# PWR_APD5052.net
KiCad netlist of a schematic drawn in Altium Designer
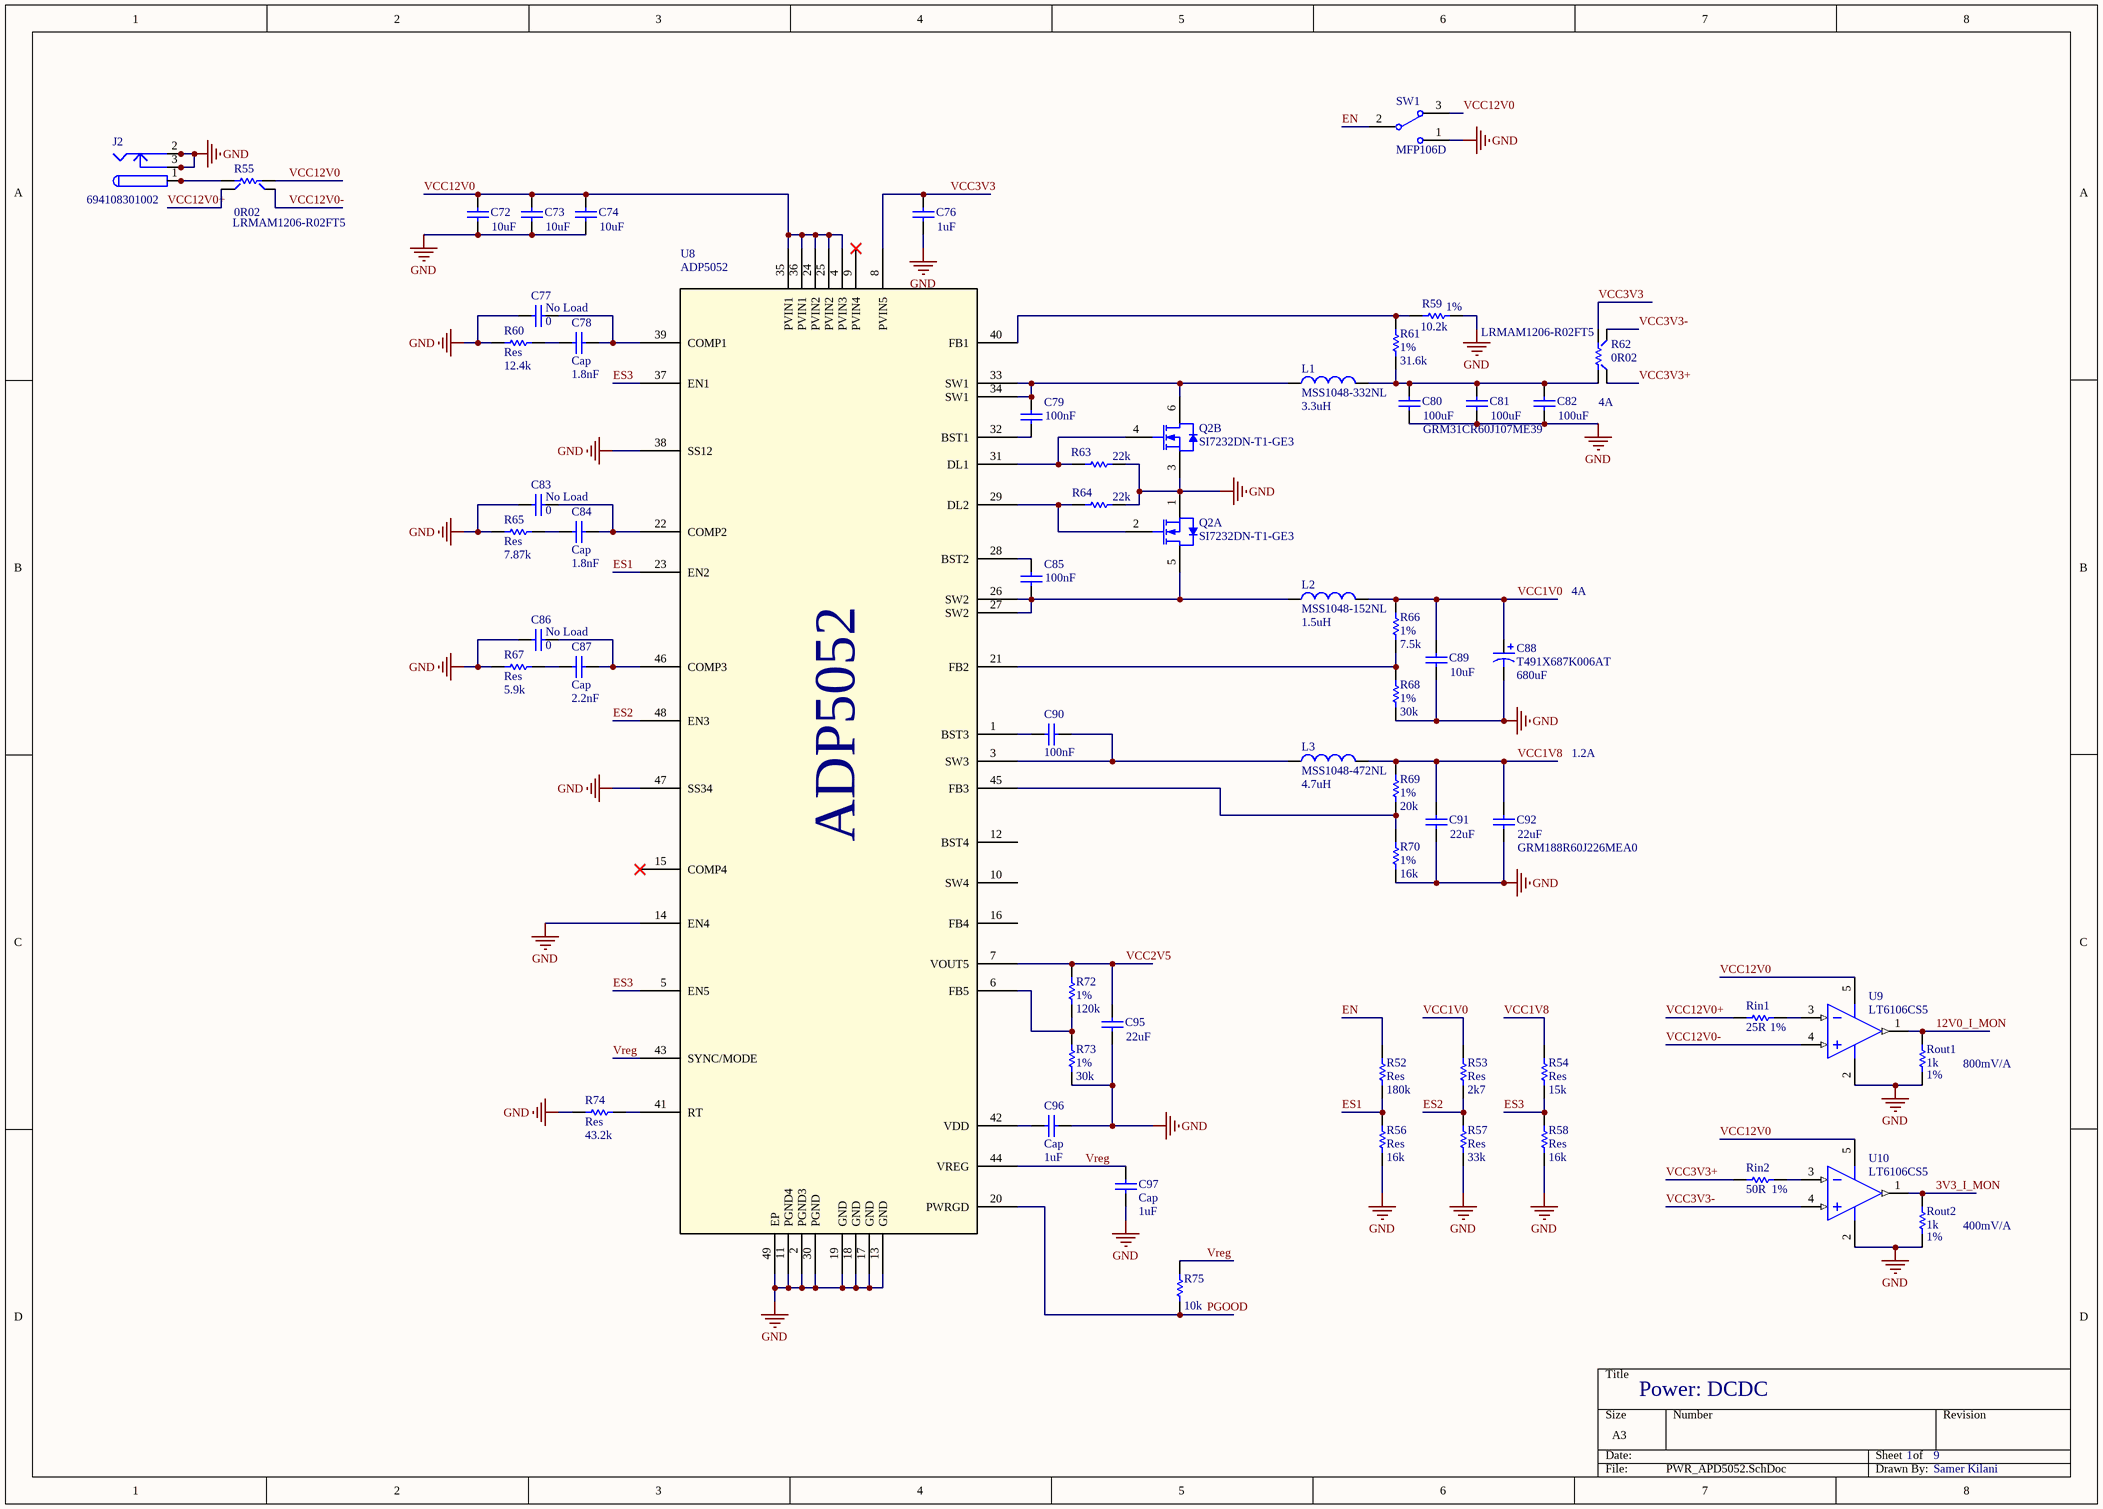
[diagram p0: PWR_APD5052.SchDoc]

(export (version "E")
  (design (tool "Eeschema 10.0.6"))
  (components
    (comp (ref "C72")
      (value "10uF")
      (footprint "C0805")
      (description "Capacitor")
      (fields (field (name "PUBLISHER") "Altium Limited"))
      (libsource (lib "atfclib") (part "Cap"))
    )
    (comp (ref "C73")
      (value "10uF")
      (footprint "C0805")
      (description "Capacitor")
      (fields (field (name "PUBLISHER") "Altium Limited"))
      (libsource (lib "atfclib") (part "Cap"))
    )
    (comp (ref "C74")
      (value "10uF")
      (footprint "C0805")
      (description "Capacitor")
      (fields (field (name "Comment") "Cap") (field (name "PUBLISHER") "Altium Limited"))
      (libsource (lib "atfclib") (part "Cap"))
    )
    (comp (ref "C76")
      (value "1uF")
      (footprint "C0402")
      (description "Capacitor")
      (fields (field (name "PUBLISHER") "Altium Limited"))
      (libsource (lib "atfclib") (part "Cap"))
    )
    (comp (ref "C77")
      (value "No Load")
      (footprint "C0402")
      (description "Capacitor")
      (fields (field (name "ALTIUM_VALUE") "0") (field (name "PUBLISHER") "Altium Limited"))
      (libsource (lib "atfclib") (part "Cap"))
    )
    (comp (ref "C78")
      (value "Cap")
      (footprint "C0402")
      (description "Capacitor")
      (fields (field (name "ALTIUM_VALUE") "1.8nF") (field (name "PUBLISHER") "Altium Limited"))
      (libsource (lib "atfclib") (part "Cap"))
    )
    (comp (ref "C79")
      (value "100nF")
      (footprint "C0402")
      (description "Capacitor")
      (fields (field (name "Comment") "Cap") (field (name "PUBLISHER") "Altium Limited"))
      (libsource (lib "atfclib") (part "Cap"))
    )
    (comp (ref "C80")
      (value "GRM31CR60J107ME39")
      (footprint "C1206")
      (description "Capacitor")
      (fields (field (name "ALTIUM_VALUE") "100uF") (field (name "PUBLISHER") "Altium Limited"))
      (libsource (lib "atfclib") (part "Cap"))
    )
    (comp (ref "C81")
      (value "100uF")
      (footprint "C1206")
      (description "Capacitor")
      (fields (field (name "Comment") "GRM31CR60J107ME39") (field (name "PUBLISHER") "Altium Limited"))
      (libsource (lib "atfclib") (part "Cap"))
    )
    (comp (ref "C82")
      (value "100uF")
      (footprint "C1206")
      (description "Capacitor")
      (fields (field (name "Comment") "GRM31CR60J107ME39") (field (name "PUBLISHER") "Altium Limited"))
      (libsource (lib "atfclib") (part "Cap"))
    )
    (comp (ref "C83")
      (value "No Load")
      (footprint "C0402")
      (description "Capacitor")
      (fields (field (name "ALTIUM_VALUE") "0") (field (name "PUBLISHER") "Altium Limited"))
      (libsource (lib "atfclib") (part "Cap"))
    )
    (comp (ref "C84")
      (value "Cap")
      (footprint "C0402")
      (description "Capacitor")
      (fields (field (name "ALTIUM_VALUE") "1.8nF") (field (name "PUBLISHER") "Altium Limited"))
      (libsource (lib "atfclib") (part "Cap"))
    )
    (comp (ref "C85")
      (value "100nF")
      (footprint "C0402")
      (description "Capacitor")
      (fields (field (name "Comment") "Cap") (field (name "PUBLISHER") "Altium Limited"))
      (libsource (lib "atfclib") (part "Cap"))
    )
    (comp (ref "C86")
      (value "No Load")
      (footprint "C0402")
      (description "Capacitor")
      (fields (field (name "ALTIUM_VALUE") "0") (field (name "PUBLISHER") "Altium Limited"))
      (libsource (lib "atfclib") (part "Cap"))
    )
    (comp (ref "C87")
      (value "Cap")
      (footprint "C0402")
      (description "Capacitor")
      (fields (field (name "ALTIUM_VALUE") "2.2nF") (field (name "PUBLISHER") "Altium Limited"))
      (libsource (lib "atfclib") (part "Cap"))
    )
    (comp (ref "C88")
      (value "T491X687K006AT")
      (footprint "C7343")
      (description "Polarized Capacitor (Surface Mount)")
      (fields (field (name "ALTIUM_VALUE") "680uF") (field (name "PUBLISHER") "Altium Limited"))
      (libsource (lib "Miscellaneous Devices") (part "Cap Pol3"))
    )
    (comp (ref "C89")
      (value "10uF")
      (footprint "C0603")
      (description "Capacitor")
      (fields (field (name "Comment") "Cap") (field (name "PUBLISHER") "Altium Limited"))
      (libsource (lib "atfclib") (part "Cap"))
    )
    (comp (ref "C90")
      (value "100nF")
      (footprint "C0402")
      (description "Capacitor")
      (fields (field (name "Comment") "Cap") (field (name "PUBLISHER") "Altium Limited"))
      (libsource (lib "atfclib") (part "Cap"))
    )
    (comp (ref "C91")
      (value "22uF")
      (footprint "C0603")
      (description "Capacitor")
      (fields (field (name "Comment") "GRM188R60J226MEA0") (field (name "PUBLISHER") "Altium Limited"))
      (libsource (lib "atfclib") (part "Cap"))
    )
    (comp (ref "C92")
      (value "GRM188R60J226MEA0")
      (footprint "C0603")
      (description "Capacitor")
      (fields (field (name "ALTIUM_VALUE") "22uF") (field (name "PUBLISHER") "Altium Limited"))
      (libsource (lib "atfclib") (part "Cap"))
    )
    (comp (ref "C95")
      (value "22uF")
      (footprint "C0603")
      (description "Capacitor")
      (fields (field (name "Comment") "Cap") (field (name "PUBLISHER") "Altium Limited"))
      (libsource (lib "atfclib") (part "Cap"))
    )
    (comp (ref "C96")
      (value "Cap")
      (footprint "C0402")
      (description "Capacitor")
      (fields (field (name "ALTIUM_VALUE") "1uF") (field (name "PUBLISHER") "Altium Limited"))
      (libsource (lib "atfclib") (part "Cap"))
    )
    (comp (ref "C97")
      (value "Cap")
      (footprint "C0402")
      (description "Capacitor")
      (fields (field (name "ALTIUM_VALUE") "1uF") (field (name "PUBLISHER") "Altium Limited"))
      (libsource (lib "atfclib") (part "Cap"))
    )
    (comp (ref "J2")
      (value "694108301002")
      (footprint "KLD-0202")
      (description "Low Voltage Power Supply Connector")
      (fields (field (name "PUBLISHER") "Altium Limited"))
      (libsource (lib "atfclib") (part "PWR2.5"))
    )
    (comp (ref "L1")
      (value "MSS1048-332NL")
      (footprint "MSS1048")
      (description "Inductor")
      (fields (field (name "ALTIUM_VALUE") "3.3uH") (field (name "PUBLISHER") "Altium Limited"))
      (libsource (lib "atfclib") (part "Inductor"))
    )
    (comp (ref "L2")
      (value "MSS1048-152NL")
      (footprint "MSS1048")
      (description "Inductor")
      (fields (field (name "ALTIUM_VALUE") "1.5uH") (field (name "PUBLISHER") "Altium Limited"))
      (libsource (lib "atfclib") (part "Inductor"))
    )
    (comp (ref "L3")
      (value "MSS1048-472NL")
      (footprint "MSS1048")
      (description "Inductor")
      (fields (field (name "ALTIUM_VALUE") "4.7uH") (field (name "PUBLISHER") "Altium Limited"))
      (libsource (lib "atfclib") (part "Inductor"))
    )
    (comp (ref "Q2")
      (value "SI7232DN-T1-GE3")
      (footprint "1212-8dual")
      (libsource (lib "atfclib") (part "SI7232DN-T1-GE3"))
    )
    (comp (ref "R52")
      (value "Res")
      (footprint "R0402")
      (description "Resistor")
      (fields (field (name "ALTIUM_VALUE") "180k"))
      (libsource (lib "atfclib") (part "Res"))
    )
    (comp (ref "R53")
      (value "Res")
      (footprint "R0402")
      (description "Resistor")
      (fields (field (name "ALTIUM_VALUE") "2k7"))
      (libsource (lib "atfclib") (part "Res"))
    )
    (comp (ref "R54")
      (value "Res")
      (footprint "R0402")
      (description "Resistor")
      (fields (field (name "ALTIUM_VALUE") "15k"))
      (libsource (lib "atfclib") (part "Res"))
    )
    (comp (ref "R55")
      (value "LRMAM1206-R02FT5")
      (footprint "LRMA1206")
      (description "Resistor")
      (fields (field (name "ALTIUM_VALUE") "0R02"))
      (libsource (lib "atfclib") (part "Res_sense"))
    )
    (comp (ref "R56")
      (value "Res")
      (footprint "R0402")
      (description "Resistor")
      (fields (field (name "ALTIUM_VALUE") "16k"))
      (libsource (lib "atfclib") (part "Res"))
    )
    (comp (ref "R57")
      (value "Res")
      (footprint "R0402")
      (description "Resistor")
      (fields (field (name "ALTIUM_VALUE") "33k"))
      (libsource (lib "atfclib") (part "Res"))
    )
    (comp (ref "R58")
      (value "Res")
      (footprint "R0402")
      (description "Resistor")
      (fields (field (name "ALTIUM_VALUE") "16k"))
      (libsource (lib "atfclib") (part "Res"))
    )
    (comp (ref "R59")
      (value "10.2k")
      (footprint "R0402")
      (description "Resistor")
      (fields (field (name "TOLERANCE") "1%") (field (name "Comment") "Res"))
      (libsource (lib "atfclib") (part "Res"))
    )
    (comp (ref "R60")
      (value "Res")
      (footprint "R0402")
      (description "Resistor")
      (fields (field (name "ALTIUM_VALUE") "12.4k"))
      (libsource (lib "atfclib") (part "Res"))
    )
    (comp (ref "R61")
      (value "31.6k")
      (footprint "R0402")
      (description "Resistor")
      (fields (field (name "TOLERANCE") "1%") (field (name "Comment") "Res"))
      (libsource (lib "atfclib") (part "Res"))
    )
    (comp (ref "R62")
      (value "LRMAM1206-R02FT5")
      (footprint "LRMA1206")
      (description "Resistor")
      (fields (field (name "ALTIUM_VALUE") "0R02"))
      (libsource (lib "atfclib") (part "Res_sense"))
    )
    (comp (ref "R63")
      (value "22k")
      (footprint "R0402")
      (description "Resistor")
      (fields (field (name "Comment") "Res"))
      (libsource (lib "atfclib") (part "Res"))
    )
    (comp (ref "R64")
      (value "22k")
      (footprint "R0402")
      (description "Resistor")
      (fields (field (name "Comment") "Res"))
      (libsource (lib "atfclib") (part "Res"))
    )
    (comp (ref "R65")
      (value "Res")
      (footprint "R0402")
      (description "Resistor")
      (fields (field (name "ALTIUM_VALUE") "7.87k"))
      (libsource (lib "atfclib") (part "Res"))
    )
    (comp (ref "R66")
      (value "7.5k")
      (footprint "R0402")
      (description "Resistor")
      (fields (field (name "TOLERANCE") "1%") (field (name "Comment") "Res"))
      (libsource (lib "atfclib") (part "Res"))
    )
    (comp (ref "R67")
      (value "Res")
      (footprint "R0402")
      (description "Resistor")
      (fields (field (name "ALTIUM_VALUE") "5.9k"))
      (libsource (lib "atfclib") (part "Res"))
    )
    (comp (ref "R68")
      (value "30k")
      (footprint "R0402")
      (description "Resistor")
      (fields (field (name "TOLERANCE") "1%") (field (name "Comment") "Res"))
      (libsource (lib "atfclib") (part "Res"))
    )
    (comp (ref "R69")
      (value "20k")
      (footprint "R0402")
      (description "Resistor")
      (fields (field (name "TOLERANCE") "1%") (field (name "Comment") "Res"))
      (libsource (lib "atfclib") (part "Res"))
    )
    (comp (ref "R70")
      (value "16k")
      (footprint "R0402")
      (description "Resistor")
      (fields (field (name "TOLERANCE") "1%") (field (name "Comment") "Res"))
      (libsource (lib "atfclib") (part "Res"))
    )
    (comp (ref "R72")
      (value "120k")
      (footprint "R0402")
      (description "Resistor")
      (fields (field (name "TOLERANCE") "1%") (field (name "Comment") "Res"))
      (libsource (lib "atfclib") (part "Res"))
    )
    (comp (ref "R73")
      (value "30k")
      (footprint "R0402")
      (description "Resistor")
      (fields (field (name "TOLERANCE") "1%") (field (name "Comment") "Res"))
      (libsource (lib "atfclib") (part "Res"))
    )
    (comp (ref "R74")
      (value "Res")
      (footprint "R0402")
      (description "Resistor")
      (fields (field (name "ALTIUM_VALUE") "43.2k"))
      (libsource (lib "atfclib") (part "Res"))
    )
    (comp (ref "R75")
      (value "10k")
      (footprint "R0402")
      (description "Resistor")
      (fields (field (name "Comment") "Res"))
      (libsource (lib "atfclib") (part "Res"))
    )
    (comp (ref "Rin1")
      (value "25R")
      (footprint "R0402")
      (description "Resistor")
      (fields (field (name "TOLERANCE") "1%") (field (name "Comment") "Res"))
      (libsource (lib "atfclib") (part "Res"))
    )
    (comp (ref "Rin2")
      (value "50R")
      (footprint "R0402")
      (description "Resistor")
      (fields (field (name "TOLERANCE") "1%") (field (name "Comment") "Res"))
      (libsource (lib "atfclib") (part "Res"))
    )
    (comp (ref "Rout1")
      (value "1k")
      (footprint "R0402")
      (description "Resistor")
      (fields (field (name "TOLERANCE") "1%") (field (name "Comment") "Res"))
      (libsource (lib "atfclib") (part "Res"))
    )
    (comp (ref "Rout2")
      (value "1k")
      (footprint "R0402")
      (description "Resistor")
      (fields (field (name "TOLERANCE") "1%") (field (name "Comment") "Res"))
      (libsource (lib "atfclib") (part "Res"))
    )
    (comp (ref "SW1")
      (value "MFP106D")
      (footprint "MFP106D")
      (description "SPDT Subminiature Toggle Switch, Right Angle Mounting, Vertical Actuation")
      (fields (field (name "PUBLISHER") "Altium Limited"))
      (libsource (lib "Miscellaneous Devices") (part "SW-SPDT"))
    )
    (comp (ref "U8")
      (value "ADP5052")
      (footprint "CP_48_13")
      (description "Imported")
      (libsource (lib "atfclib") (part "ADP5052ACPZ-R7"))
    )
    (comp (ref "U9")
      (value "LT6106CS5")
      (footprint "LT-S5-5-TSOT-23_N")
      (fields
        (field (name "LINEAR TECHNOLOGY PART NUMBER") "LT6106")
        (field (name "MANUFACTURER") "Linear Technology")
      )
      (libsource (lib "atfclib") (part "LT6106CS5"))
    )
    (comp (ref "U10")
      (value "LT6106CS5")
      (footprint "LT-S5-5-TSOT-23_N")
      (fields
        (field (name "LINEAR TECHNOLOGY PART NUMBER") "LT6106")
        (field (name "MANUFACTURER") "Linear Technology")
      )
      (libsource (lib "atfclib") (part "LT6106CS5"))
    )
  )
  (nets
    (net (code "1") (name "/3V3_I_MON") (class "Default")
      (node (ref "Rout2") (pin "2") (pinfunction "2_2") (pintype "passive"))
      (node (ref "U10") (pin "1") (pinfunction "OUT_1") (pintype "output"))
    )
    (net (code "2") (name "/12V0_I_MON") (class "Default")
      (node (ref "Rout1") (pin "2") (pinfunction "2_2") (pintype "passive"))
      (node (ref "U9") (pin "1") (pinfunction "OUT_1") (pintype "output"))
    )
    (net (code "3") (name "/EN") (class "Default")
      (node (ref "R52") (pin "2") (pinfunction "2_2") (pintype "passive"))
      (node (ref "SW1") (pin "2") (pinfunction "2_2") (pintype "passive"))
    )
    (net (code "4") (name "/ES1") (class "Default")
      (node (ref "R52") (pin "1") (pinfunction "1_1") (pintype "passive"))
      (node (ref "R56") (pin "2") (pinfunction "2_2") (pintype "passive"))
      (node (ref "U8") (pin "23") (pinfunction "EN2_23") (pintype "passive"))
    )
    (net (code "5") (name "/ES2") (class "Default")
      (node (ref "R53") (pin "1") (pinfunction "1_1") (pintype "passive"))
      (node (ref "R57") (pin "2") (pinfunction "2_2") (pintype "passive"))
      (node (ref "U8") (pin "48") (pinfunction "EN3_48") (pintype "passive"))
    )
    (net (code "6") (name "/ES3") (class "Default")
      (node (ref "R54") (pin "1") (pinfunction "1_1") (pintype "passive"))
      (node (ref "R58") (pin "2") (pinfunction "2_2") (pintype "passive"))
      (node (ref "U8") (pin "37") (pinfunction "EN1_37") (pintype "passive"))
      (node (ref "U8") (pin "5") (pinfunction "EN5_5") (pintype "passive"))
    )
    (net (code "7") (name "/PGOOD") (class "Default")
      (node (ref "R75") (pin "1") (pinfunction "1_1") (pintype "passive"))
      (node (ref "U8") (pin "20") (pinfunction "PWRGD_20") (pintype "passive"))
    )
    (net (code "8") (name "/VCC1V0") (class "Default")
      (node (ref "C88") (pin "1") (pinfunction "1_1") (pintype "passive"))
      (node (ref "C89") (pin "2") (pinfunction "2_2") (pintype "passive"))
      (node (ref "L2") (pin "2") (pinfunction "2_2") (pintype "passive"))
      (node (ref "R53") (pin "2") (pinfunction "2_2") (pintype "passive"))
      (node (ref "R66") (pin "2") (pinfunction "2_2") (pintype "passive"))
    )
    (net (code "9") (name "/VCC1V8") (class "Default")
      (node (ref "C91") (pin "2") (pinfunction "2_2") (pintype "passive"))
      (node (ref "C92") (pin "2") (pinfunction "2_2") (pintype "passive"))
      (node (ref "L3") (pin "2") (pinfunction "2_2") (pintype "passive"))
      (node (ref "R54") (pin "2") (pinfunction "2_2") (pintype "passive"))
      (node (ref "R69") (pin "2") (pinfunction "2_2") (pintype "passive"))
    )
    (net (code "10") (name "/VCC2V5") (class "Default")
      (node (ref "C95") (pin "2") (pinfunction "2_2") (pintype "passive"))
      (node (ref "R72") (pin "2") (pinfunction "2_2") (pintype "passive"))
      (node (ref "U8") (pin "7") (pinfunction "VOUT5_7") (pintype "passive"))
    )
    (net (code "11") (name "/VCC3V3") (class "Default")
      (node (ref "C76") (pin "2") (pinfunction "2_2") (pintype "passive"))
      (node (ref "R62") (pin "2") (pinfunction "2_2") (pintype "passive"))
      (node (ref "U8") (pin "8") (pinfunction "PVIN5_8") (pintype "passive"))
    )
    (net (code "12") (name "/VCC3V3+") (class "Default")
      (node (ref "R62") (pin "3") (pinfunction "3_3") (pintype "passive"))
      (node (ref "Rin2") (pin "1") (pinfunction "1_1") (pintype "passive"))
    )
    (net (code "13") (name "/VCC3V3-") (class "Default")
      (node (ref "R62") (pin "4") (pinfunction "4_4") (pintype "passive"))
      (node (ref "U10") (pin "4") (pinfunction "+IN_4") (pintype "input"))
    )
    (net (code "14") (name "/VCC12V0") (class "Default")
      (node (ref "C72") (pin "2") (pinfunction "2_2") (pintype "passive"))
      (node (ref "C73") (pin "2") (pinfunction "2_2") (pintype "passive"))
      (node (ref "C74") (pin "2") (pinfunction "2_2") (pintype "passive"))
      (node (ref "R55") (pin "2") (pinfunction "2_2") (pintype "passive"))
      (node (ref "SW1") (pin "3") (pinfunction "3_3") (pintype "passive"))
      (node (ref "U10") (pin "5") (pinfunction "V+_5") (pintype "power_in"))
      (node (ref "U8") (pin "24") (pinfunction "PVIN2_24") (pintype "passive"))
      (node (ref "U8") (pin "25") (pinfunction "PVIN2_25") (pintype "passive"))
      (node (ref "U8") (pin "35") (pinfunction "PVIN1_35") (pintype "passive"))
      (node (ref "U8") (pin "36") (pinfunction "PVIN1_36") (pintype "passive"))
      (node (ref "U8") (pin "4") (pinfunction "PVIN3_4") (pintype "passive"))
      (node (ref "U9") (pin "5") (pinfunction "V+_5") (pintype "power_in"))
    )
    (net (code "15") (name "/VCC12V0+") (class "Default")
      (node (ref "R55") (pin "3") (pinfunction "3_3") (pintype "passive"))
      (node (ref "Rin1") (pin "1") (pinfunction "1_1") (pintype "passive"))
    )
    (net (code "16") (name "/VCC12V0-") (class "Default")
      (node (ref "R55") (pin "4") (pinfunction "4_4") (pintype "passive"))
      (node (ref "U9") (pin "4") (pinfunction "+IN_4") (pintype "input"))
    )
    (net (code "17") (name "/Vreg") (class "Default")
      (node (ref "C97") (pin "2") (pinfunction "2_2") (pintype "passive"))
      (node (ref "R75") (pin "2") (pinfunction "2_2") (pintype "passive"))
      (node (ref "U8") (pin "43") (pinfunction "SYNC/MODE_43") (pintype "passive"))
      (node (ref "U8") (pin "44") (pinfunction "VREG_44") (pintype "passive"))
    )
    (net (code "18") (name "GND") (class "Default")
      (node (ref "C72") (pin "1") (pinfunction "1_1") (pintype "passive"))
      (node (ref "C73") (pin "1") (pinfunction "1_1") (pintype "passive"))
      (node (ref "C74") (pin "1") (pinfunction "1_1") (pintype "passive"))
      (node (ref "C76") (pin "1") (pinfunction "1_1") (pintype "passive"))
      (node (ref "C77") (pin "1") (pinfunction "1_1") (pintype "passive"))
      (node (ref "C80") (pin "1") (pinfunction "1_1") (pintype "passive"))
      (node (ref "C81") (pin "1") (pinfunction "1_1") (pintype "passive"))
      (node (ref "C82") (pin "1") (pinfunction "1_1") (pintype "passive"))
      (node (ref "C83") (pin "1") (pinfunction "1_1") (pintype "passive"))
      (node (ref "C86") (pin "1") (pinfunction "1_1") (pintype "passive"))
      (node (ref "C88") (pin "2") (pinfunction "2_2") (pintype "passive"))
      (node (ref "C89") (pin "1") (pinfunction "1_1") (pintype "passive"))
      (node (ref "C91") (pin "1") (pinfunction "1_1") (pintype "passive"))
      (node (ref "C92") (pin "1") (pinfunction "1_1") (pintype "passive"))
      (node (ref "C95") (pin "1") (pinfunction "1_1") (pintype "passive"))
      (node (ref "C96") (pin "1") (pinfunction "1_1") (pintype "passive"))
      (node (ref "C97") (pin "1") (pinfunction "1_1") (pintype "passive"))
      (node (ref "J2") (pin "2") (pinfunction "2_2") (pintype "power_in"))
      (node (ref "J2") (pin "2A") (pinfunction "2A_2A") (pintype "power_in"))
      (node (ref "J2") (pin "2B") (pinfunction "2B_2B") (pintype "power_in"))
      (node (ref "J2") (pin "3") (pinfunction "3_3") (pintype "power_in"))
      (node (ref "J2") (pin "3A") (pinfunction "3A_3A") (pintype "power_in"))
      (node (ref "J2") (pin "3B") (pinfunction "3B_3B") (pintype "power_in"))
      (node (ref "Q2") (pin "1") (pinfunction "S1_1") (pintype "passive"))
      (node (ref "Q2") (pin "3") (pinfunction "S2_3") (pintype "passive"))
      (node (ref "R56") (pin "1") (pinfunction "1_1") (pintype "passive"))
      (node (ref "R57") (pin "1") (pinfunction "1_1") (pintype "passive"))
      (node (ref "R58") (pin "1") (pinfunction "1_1") (pintype "passive"))
      (node (ref "R59") (pin "2") (pinfunction "2_2") (pintype "passive"))
      (node (ref "R60") (pin "1") (pinfunction "1_1") (pintype "passive"))
      (node (ref "R63") (pin "2") (pinfunction "2_2") (pintype "passive"))
      (node (ref "R64") (pin "2") (pinfunction "2_2") (pintype "passive"))
      (node (ref "R65") (pin "1") (pinfunction "1_1") (pintype "passive"))
      (node (ref "R67") (pin "1") (pinfunction "1_1") (pintype "passive"))
      (node (ref "R68") (pin "1") (pinfunction "1_1") (pintype "passive"))
      (node (ref "R70") (pin "1") (pinfunction "1_1") (pintype "passive"))
      (node (ref "R73") (pin "1") (pinfunction "1_1") (pintype "passive"))
      (node (ref "R74") (pin "1") (pinfunction "1_1") (pintype "passive"))
      (node (ref "Rout1") (pin "1") (pinfunction "1_1") (pintype "passive"))
      (node (ref "Rout2") (pin "1") (pinfunction "1_1") (pintype "passive"))
      (node (ref "SW1") (pin "1") (pinfunction "1_1") (pintype "passive"))
      (node (ref "U10") (pin "2") (pinfunction "V-_2") (pintype "power_in"))
      (node (ref "U8") (pin "11") (pinfunction "PGND4_11") (pintype "passive"))
      (node (ref "U8") (pin "13") (pinfunction "GND_13") (pintype "passive"))
      (node (ref "U8") (pin "14") (pinfunction "EN4_14") (pintype "passive"))
      (node (ref "U8") (pin "17") (pinfunction "GND_17") (pintype "passive"))
      (node (ref "U8") (pin "18") (pinfunction "GND_18") (pintype "passive"))
      (node (ref "U8") (pin "19") (pinfunction "GND_19") (pintype "passive"))
      (node (ref "U8") (pin "2") (pinfunction "PGND3_2") (pintype "passive"))
      (node (ref "U8") (pin "30") (pinfunction "PGND_30") (pintype "passive"))
      (node (ref "U8") (pin "38") (pinfunction "SS12_38") (pintype "passive"))
      (node (ref "U8") (pin "47") (pinfunction "SS34_47") (pintype "passive"))
      (node (ref "U8") (pin "49") (pinfunction "EP_49") (pintype "passive"))
      (node (ref "U9") (pin "2") (pinfunction "V-_2") (pintype "power_in"))
    )
    (net (code "19") (name "Net-(C78-Pad1)") (class "Default")
      (node (ref "C78") (pin "1") (pinfunction "1_1") (pintype "passive"))
      (node (ref "R60") (pin "2") (pinfunction "2_2") (pintype "passive"))
    )
    (net (code "20") (name "Net-(C80-Pad2)") (class "Default")
      (node (ref "C80") (pin "2") (pinfunction "2_2") (pintype "passive"))
      (node (ref "C81") (pin "2") (pinfunction "2_2") (pintype "passive"))
      (node (ref "C82") (pin "2") (pinfunction "2_2") (pintype "passive"))
      (node (ref "L1") (pin "2") (pinfunction "2_2") (pintype "passive"))
      (node (ref "R61") (pin "1") (pinfunction "1_1") (pintype "passive"))
      (node (ref "R62") (pin "1") (pinfunction "1_1") (pintype "passive"))
    )
    (net (code "21") (name "Net-(C84-Pad1)") (class "Default")
      (node (ref "C84") (pin "1") (pinfunction "1_1") (pintype "passive"))
      (node (ref "R65") (pin "2") (pinfunction "2_2") (pintype "passive"))
    )
    (net (code "22") (name "Net-(C87-Pad1)") (class "Default")
      (node (ref "C87") (pin "1") (pinfunction "1_1") (pintype "passive"))
      (node (ref "R67") (pin "2") (pinfunction "2_2") (pintype "passive"))
    )
    (net (code "23") (name "Net-(J2-Pad1)") (class "Default")
      (node (ref "J2") (pin "1") (pinfunction "1_1") (pintype "power_in"))
      (node (ref "J2") (pin "1A") (pinfunction "1A_1A") (pintype "power_in"))
      (node (ref "J2") (pin "1B") (pinfunction "1B_1B") (pintype "power_in"))
      (node (ref "R55") (pin "1") (pinfunction "1_1") (pintype "passive"))
    )
    (net (code "24") (name "Net-(Q2A-D1)") (class "Default")
      (node (ref "C85") (pin "1") (pinfunction "1_1") (pintype "passive"))
      (node (ref "L2") (pin "1") (pinfunction "1_1") (pintype "passive"))
      (node (ref "Q2") (pin "5") (pinfunction "D1_5") (pintype "passive"))
      (node (ref "U8") (pin "26") (pinfunction "SW2_26") (pintype "passive"))
      (node (ref "U8") (pin "27") (pinfunction "SW2_27") (pintype "passive"))
    )
    (net (code "25") (name "Net-(Q2A-G1)") (class "Default")
      (node (ref "Q2") (pin "2") (pinfunction "G1_2") (pintype "passive"))
      (node (ref "R64") (pin "1") (pinfunction "1_1") (pintype "passive"))
      (node (ref "U8") (pin "29") (pinfunction "DL2_29") (pintype "passive"))
    )
    (net (code "26") (name "Net-(Q2B-D2)") (class "Default")
      (node (ref "C79") (pin "2") (pinfunction "2_2") (pintype "passive"))
      (node (ref "L1") (pin "1") (pinfunction "1_1") (pintype "passive"))
      (node (ref "Q2") (pin "6") (pinfunction "D2_6") (pintype "passive"))
      (node (ref "U8") (pin "33") (pinfunction "SW1_33") (pintype "passive"))
      (node (ref "U8") (pin "34") (pinfunction "SW1_34") (pintype "passive"))
    )
    (net (code "27") (name "Net-(Q2B-G2)") (class "Default")
      (node (ref "Q2") (pin "4") (pinfunction "G2_4") (pintype "passive"))
      (node (ref "R63") (pin "1") (pinfunction "1_1") (pintype "passive"))
      (node (ref "U8") (pin "31") (pinfunction "DL1_31") (pintype "passive"))
    )
    (net (code "28") (name "Net-(U8-BST1)") (class "Default")
      (node (ref "C79") (pin "1") (pinfunction "1_1") (pintype "passive"))
      (node (ref "U8") (pin "32") (pinfunction "BST1_32") (pintype "passive"))
    )
    (net (code "29") (name "Net-(U8-BST2)") (class "Default")
      (node (ref "C85") (pin "2") (pinfunction "2_2") (pintype "passive"))
      (node (ref "U8") (pin "28") (pinfunction "BST2_28") (pintype "passive"))
    )
    (net (code "30") (name "Net-(U8-BST3)") (class "Default")
      (node (ref "C90") (pin "2") (pinfunction "2_2") (pintype "passive"))
      (node (ref "U8") (pin "1") (pinfunction "BST3_1") (pintype "passive"))
    )
    (net (code "31") (name "Net-(U8-COMP1)") (class "Default")
      (node (ref "C77") (pin "2") (pinfunction "2_2") (pintype "passive"))
      (node (ref "C78") (pin "2") (pinfunction "2_2") (pintype "passive"))
      (node (ref "U8") (pin "39") (pinfunction "COMP1_39") (pintype "passive"))
    )
    (net (code "32") (name "Net-(U8-COMP2)") (class "Default")
      (node (ref "C83") (pin "2") (pinfunction "2_2") (pintype "passive"))
      (node (ref "C84") (pin "2") (pinfunction "2_2") (pintype "passive"))
      (node (ref "U8") (pin "22") (pinfunction "COMP2_22") (pintype "passive"))
    )
    (net (code "33") (name "Net-(U8-COMP3)") (class "Default")
      (node (ref "C86") (pin "2") (pinfunction "2_2") (pintype "passive"))
      (node (ref "C87") (pin "2") (pinfunction "2_2") (pintype "passive"))
      (node (ref "U8") (pin "46") (pinfunction "COMP3_46") (pintype "passive"))
    )
    (net (code "34") (name "Net-(U8-FB1)") (class "Default")
      (node (ref "R59") (pin "1") (pinfunction "1_1") (pintype "passive"))
      (node (ref "R61") (pin "2") (pinfunction "2_2") (pintype "passive"))
      (node (ref "U8") (pin "40") (pinfunction "FB1_40") (pintype "passive"))
    )
    (net (code "35") (name "Net-(U8-FB2)") (class "Default")
      (node (ref "R66") (pin "1") (pinfunction "1_1") (pintype "passive"))
      (node (ref "R68") (pin "2") (pinfunction "2_2") (pintype "passive"))
      (node (ref "U8") (pin "21") (pinfunction "FB2_21") (pintype "passive"))
    )
    (net (code "36") (name "Net-(U8-FB3)") (class "Default")
      (node (ref "R69") (pin "1") (pinfunction "1_1") (pintype "passive"))
      (node (ref "R70") (pin "2") (pinfunction "2_2") (pintype "passive"))
      (node (ref "U8") (pin "45") (pinfunction "FB3_45") (pintype "passive"))
    )
    (net (code "37") (name "Net-(U8-FB5)") (class "Default")
      (node (ref "R72") (pin "1") (pinfunction "1_1") (pintype "passive"))
      (node (ref "R73") (pin "2") (pinfunction "2_2") (pintype "passive"))
      (node (ref "U8") (pin "6") (pinfunction "FB5_6") (pintype "passive"))
    )
    (net (code "38") (name "Net-(U8-RT)") (class "Default")
      (node (ref "R74") (pin "2") (pinfunction "2_2") (pintype "passive"))
      (node (ref "U8") (pin "41") (pinfunction "RT_41") (pintype "passive"))
    )
    (net (code "39") (name "Net-(U8-SW3)") (class "Default")
      (node (ref "C90") (pin "1") (pinfunction "1_1") (pintype "passive"))
      (node (ref "L3") (pin "1") (pinfunction "1_1") (pintype "passive"))
      (node (ref "U8") (pin "3") (pinfunction "SW3_3") (pintype "passive"))
    )
    (net (code "40") (name "Net-(U8-VDD)") (class "Default")
      (node (ref "C96") (pin "2") (pinfunction "2_2") (pintype "passive"))
      (node (ref "U8") (pin "42") (pinfunction "VDD_42") (pintype "passive"))
    )
    (net (code "41") (name "Net-(U9--IN)") (class "Default")
      (node (ref "Rin1") (pin "2") (pinfunction "2_2") (pintype "passive"))
      (node (ref "U9") (pin "3") (pinfunction "-IN_3") (pintype "input"))
    )
    (net (code "42") (name "Net-(U10--IN)") (class "Default")
      (node (ref "Rin2") (pin "2") (pinfunction "2_2") (pintype "passive"))
      (node (ref "U10") (pin "3") (pinfunction "-IN_3") (pintype "input"))
    )
    (net (code "43") (name "unconnected-(U8-BST4-Pad12)") (class "Default")
      (node (ref "U8") (pin "12") (pinfunction "BST4_12") (pintype "passive"))
    )
    (net (code "44") (name "unconnected-(U8-COMP4-Pad15)") (class "Default")
      (node (ref "U8") (pin "15") (pinfunction "COMP4_15") (pintype "passive+no_connect"))
    )
    (net (code "45") (name "unconnected-(U8-FB4-Pad16)") (class "Default")
      (node (ref "U8") (pin "16") (pinfunction "FB4_16") (pintype "passive"))
    )
    (net (code "46") (name "unconnected-(U8-PVIN4-Pad9)") (class "Default")
      (node (ref "U8") (pin "9") (pinfunction "PVIN4_9") (pintype "passive+no_connect"))
    )
    (net (code "47") (name "unconnected-(U8-SW4-Pad10)") (class "Default")
      (node (ref "U8") (pin "10") (pinfunction "SW4_10") (pintype "passive"))
    )
  )
)
